# PCB_design.net
KiCad netlist of a schematic drawn in EAGLE
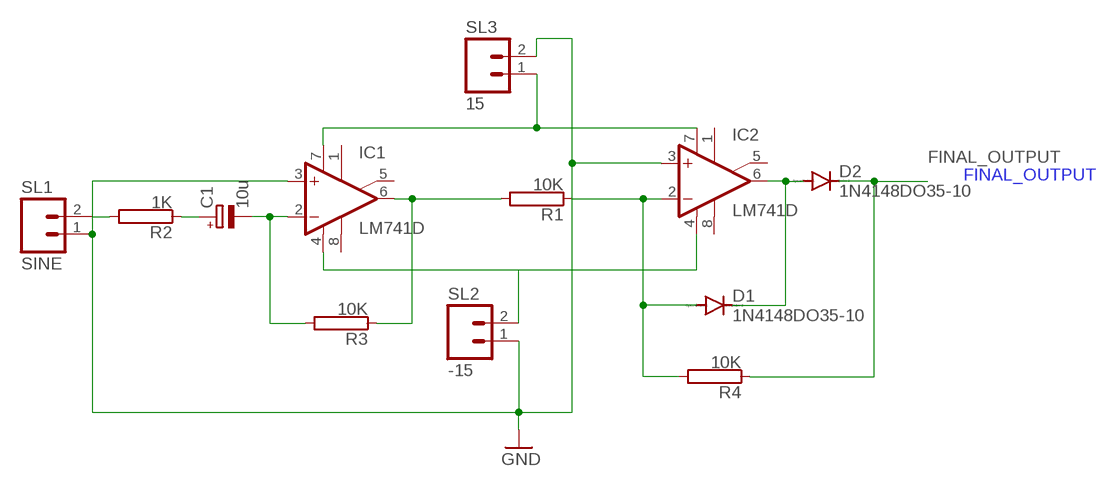
[diagram p0: schematic, sheet 1]

(export (version "E")
  (design (tool "Eeschema 10.0.6"))
  (components
    (comp (ref "C1")
      (value "10u")
      (footprint "eagle-import:E2,5-5")
      (libsource (lib "eagle-import") (part "CPOL-EUE2.5-5"))
    )
    (comp (ref "D1")
      (value "1N4148DO35-10")
      (footprint "eagle-import:DO35-10")
      (libsource (lib "eagle-import") (part "1N4148DO35-10"))
    )
    (comp (ref "D2")
      (value "1N4148DO35-10")
      (footprint "eagle-import:DO35-10")
      (libsource (lib "eagle-import") (part "1N4148DO35-10"))
    )
    (comp (ref "IC1")
      (value "LM741D")
      (footprint "eagle-import:SO08")
      (libsource (lib "eagle-import") (part "741DLM"))
    )
    (comp (ref "IC2")
      (value "LM741D")
      (footprint "eagle-import:SO08")
      (libsource (lib "eagle-import") (part "741DLM"))
    )
    (comp (ref "R1")
      (value "10K")
      (footprint "eagle-import:TO-247-2V")
      (libsource (lib "eagle-import") (part "RMG100-V"))
    )
    (comp (ref "R2")
      (value "1K")
      (footprint "eagle-import:TO-247-2V")
      (libsource (lib "eagle-import") (part "RMG100-V"))
    )
    (comp (ref "R3")
      (value "10K")
      (footprint "eagle-import:TO-247-2V")
      (libsource (lib "eagle-import") (part "RMG100-V"))
    )
    (comp (ref "R4")
      (value "10K")
      (footprint "eagle-import:TO-247-2V")
      (libsource (lib "eagle-import") (part "RMG100-V"))
    )
    (comp (ref "SL1")
      (value "SINE")
      (footprint "eagle-import:02P")
      (libsource (lib "eagle-import") (part "M02"))
    )
    (comp (ref "SL2")
      (value "-15")
      (footprint "eagle-import:02P")
      (libsource (lib "eagle-import") (part "M02"))
    )
    (comp (ref "SL3")
      (value "15")
      (footprint "eagle-import:02P")
      (libsource (lib "eagle-import") (part "M02"))
    )
  )
  (nets
    (net (code "1") (name "/FINAL_OUTPUT") (class "Default")
      (node (ref "D2") (pin "C") (pinfunction "C_C") (pintype "passive"))
      (node (ref "R4") (pin "1") (pinfunction "1_1") (pintype "passive"))
    )
    (net (code "2") (name "GND") (class "Default")
      (node (ref "IC1") (pin "3") (pinfunction "+IN_3") (pintype "input"))
      (node (ref "IC2") (pin "3") (pinfunction "+IN_3") (pintype "input"))
      (node (ref "SL1") (pin "1") (pinfunction "1_1") (pintype "passive"))
      (node (ref "SL2") (pin "1") (pinfunction "1_1") (pintype "passive"))
      (node (ref "SL3") (pin "2") (pinfunction "2_2") (pintype "passive"))
    )
    (net (code "3") (name "Net-(C1-Pad+)") (class "Default")
      (node (ref "C1") (pin "+") (pinfunction "+_+") (pintype "passive"))
      (node (ref "R2") (pin "1") (pinfunction "1_1") (pintype "passive"))
    )
    (net (code "4") (name "Net-(IC1--IN)") (class "Default")
      (node (ref "C1") (pin "-") (pinfunction "-_-") (pintype "passive"))
      (node (ref "IC1") (pin "2") (pinfunction "-IN_2") (pintype "input"))
      (node (ref "R3") (pin "2") (pinfunction "2_2") (pintype "passive"))
    )
    (net (code "5") (name "Net-(IC1-OUT)") (class "Default")
      (node (ref "IC1") (pin "6") (pinfunction "OUT_6") (pintype "output"))
      (node (ref "R1") (pin "2") (pinfunction "2_2") (pintype "passive"))
      (node (ref "R3") (pin "1") (pinfunction "1_1") (pintype "passive"))
    )
    (net (code "6") (name "Net-(IC1-V+)") (class "Default")
      (node (ref "IC1") (pin "7") (pinfunction "V+_7") (pintype "power_in"))
      (node (ref "IC2") (pin "7") (pinfunction "V+_7") (pintype "power_in"))
      (node (ref "SL3") (pin "1") (pinfunction "1_1") (pintype "passive"))
    )
    (net (code "7") (name "Net-(IC1-V-)") (class "Default")
      (node (ref "IC1") (pin "4") (pinfunction "V-_4") (pintype "power_in"))
      (node (ref "IC2") (pin "4") (pinfunction "V-_4") (pintype "power_in"))
      (node (ref "SL2") (pin "2") (pinfunction "2_2") (pintype "passive"))
    )
    (net (code "8") (name "Net-(IC2--IN)") (class "Default")
      (node (ref "D1") (pin "A") (pinfunction "A_A") (pintype "passive"))
      (node (ref "IC2") (pin "2") (pinfunction "-IN_2") (pintype "input"))
      (node (ref "R1") (pin "1") (pinfunction "1_1") (pintype "passive"))
      (node (ref "R4") (pin "2") (pinfunction "2_2") (pintype "passive"))
    )
    (net (code "9") (name "Net-(IC2-OUT)") (class "Default")
      (node (ref "D1") (pin "C") (pinfunction "C_C") (pintype "passive"))
      (node (ref "D2") (pin "A") (pinfunction "A_A") (pintype "passive"))
      (node (ref "IC2") (pin "6") (pinfunction "OUT_6") (pintype "output"))
    )
    (net (code "10") (name "Net-(R2-Pad2)") (class "Default")
      (node (ref "R2") (pin "2") (pinfunction "2_2") (pintype "passive"))
      (node (ref "SL1") (pin "2") (pinfunction "2_2") (pintype "passive"))
    )
    (net (code "11") (name "unconnected-(IC1-ON1-Pad1)") (class "Default")
      (node (ref "IC1") (pin "1") (pinfunction "ON1_1") (pintype "passive"))
    )
    (net (code "12") (name "unconnected-(IC1-ON2-Pad5)") (class "Default")
      (node (ref "IC1") (pin "5") (pinfunction "ON2_5") (pintype "passive"))
    )
    (net (code "13") (name "unconnected-(IC1-OPT-Pad8)") (class "Default")
      (node (ref "IC1") (pin "8") (pinfunction "OPT_8") (pintype "passive"))
    )
    (net (code "14") (name "unconnected-(IC2-ON1-Pad1)") (class "Default")
      (node (ref "IC2") (pin "1") (pinfunction "ON1_1") (pintype "passive"))
    )
    (net (code "15") (name "unconnected-(IC2-ON2-Pad5)") (class "Default")
      (node (ref "IC2") (pin "5") (pinfunction "ON2_5") (pintype "passive"))
    )
    (net (code "16") (name "unconnected-(IC2-OPT-Pad8)") (class "Default")
      (node (ref "IC2") (pin "8") (pinfunction "OPT_8") (pintype "passive"))
    )
  )
)
